# ethernet-connector.net
KiCad netlist of a schematic drawn in Altium Designer
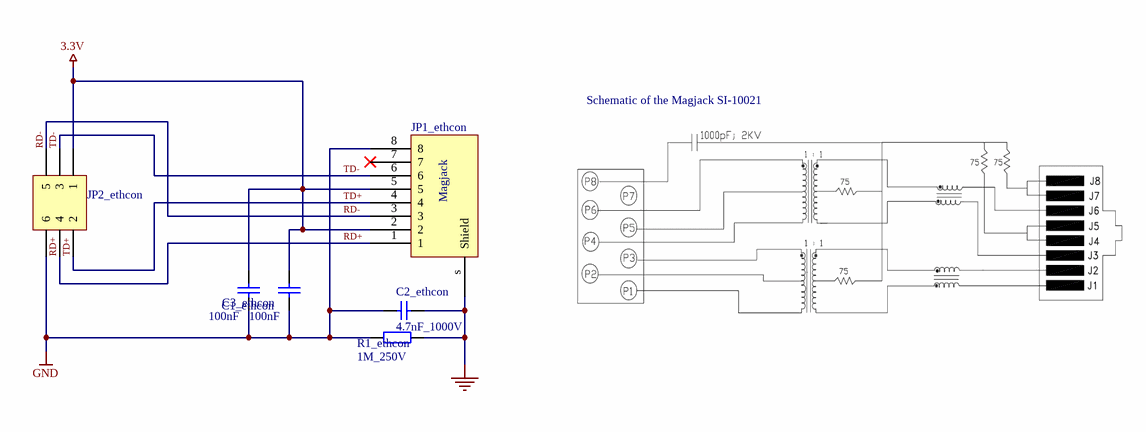
[diagram p0: ethernet-connector.SchDoc]

(export (version "E")
  (design (tool "Eeschema 10.0.6"))
  (components
    (comp (ref "1_ethcon")
      (value "CC License")
      (footprint "CC-License")
      (libsource (lib "gecko3-user") (part "CC License"))
    )
    (comp (ref "C1_ethcon")
      (value "100nF")
      (footprint "0402")
      (description "Capacitor")
      (fields
        (field (name "MANUFACTURER") "Murata")
        (field (name "PART NUMBER") "GRM155R71C104KA88D")
        (field (name "PUBLISHER") "Altium Limited")
      )
      (libsource (lib "Miscellaneous Devices") (part "Cap"))
    )
    (comp (ref "C2_ethcon")
      (value "4.7nF_1000V")
      (footprint "c-r5")
      (fields
        (field (name "MANUFACTURER") "Murata")
        (field (name "PART NUMBER") "DEBF33A472ZC1B")
        (field (name "Comment") "C")
      )
      (libsource (lib "gecko3-user") (part "C"))
    )
    (comp (ref "C3_ethcon")
      (value "100nF")
      (footprint "0402")
      (description "Capacitor")
      (fields
        (field (name "MANUFACTURER") "Murata")
        (field (name "PART NUMBER") "GRM155R71C104KA88D")
        (field (name "PUBLISHER") "Altium Limited")
      )
      (libsource (lib "Miscellaneous Devices") (part "Cap"))
    )
    (comp (ref "JP1_ethcon")
      (value "SI-10021")
      (footprint "SI-10021")
      (description "MagJack from Bel Stewart, single port RJ45 with magnetics, without LED's")
      (fields (field (name "MANUFACTURER") "Stewart"))
      (libsource (lib "gecko3-user") (part "SI-10021"))
    )
    (comp (ref "JP2_ethcon")
      (value "M22-2540305")
      (footprint "M22-2540305")
      (fields (field (name "MANUFACTURER") "HARWIN") (field (name "PART NUMBER") "M22F2040305"))
      (libsource (lib "gecko3-user") (part "M22-2540305"))
    )
    (comp (ref "R1_ethcon")
      (value "1M_250V")
      (footprint "CC3216-1206")
      (description "Resistor")
      (fields
        (field (name "MANUFACTURER") "Multicomp")
        (field (name "PART NUMBER") "MC 0.125W 1206 1% 1M")
        (field (name "PUBLISHER") "Altium Limited")
      )
      (libsource (lib "Miscellaneous Devices") (part "Res2"))
    )
  )
  (nets
    (net (code "1") (name "/RD+") (class "Default")
      (node (ref "JP1_ethcon") (pin "1") (pinfunction "1_1") (pintype "passive"))
      (node (ref "JP2_ethcon") (pin "4") (pinfunction "4_4") (pintype "passive"))
    )
    (net (code "2") (name "/RD-") (class "Default")
      (node (ref "JP1_ethcon") (pin "3") (pinfunction "3_3") (pintype "passive"))
      (node (ref "JP2_ethcon") (pin "5") (pinfunction "5_5") (pintype "passive"))
    )
    (net (code "3") (name "/TD+") (class "Default")
      (node (ref "JP1_ethcon") (pin "4") (pinfunction "4_4") (pintype "passive"))
      (node (ref "JP2_ethcon") (pin "2") (pinfunction "2_2") (pintype "passive"))
    )
    (net (code "4") (name "/TD-") (class "Default")
      (node (ref "JP1_ethcon") (pin "6") (pinfunction "6_6") (pintype "passive"))
      (node (ref "JP2_ethcon") (pin "3") (pinfunction "3_3") (pintype "passive"))
    )
    (net (code "5") (name "3.3V") (class "Default")
      (node (ref "C1_ethcon") (pin "2") (pinfunction "2_2") (pintype "passive"))
      (node (ref "C3_ethcon") (pin "2") (pinfunction "2_2") (pintype "passive"))
      (node (ref "JP1_ethcon") (pin "2") (pinfunction "2_2") (pintype "passive"))
      (node (ref "JP1_ethcon") (pin "5") (pinfunction "5_5") (pintype "passive"))
      (node (ref "JP2_ethcon") (pin "1") (pinfunction "1_1") (pintype "passive"))
    )
    (net (code "6") (name "Earth") (class "Default")
      (node (ref "C2_ethcon") (pin "1") (pinfunction "1_1") (pintype "passive"))
      (node (ref "JP1_ethcon") (pin "s") (pinfunction "Shield_s") (pintype "passive"))
      (node (ref "R1_ethcon") (pin "1") (pinfunction "1_1") (pintype "passive"))
    )
    (net (code "7") (name "GND") (class "Default")
      (node (ref "C1_ethcon") (pin "1") (pinfunction "1_1") (pintype "passive"))
      (node (ref "C2_ethcon") (pin "2") (pinfunction "2_2") (pintype "passive"))
      (node (ref "C3_ethcon") (pin "1") (pinfunction "1_1") (pintype "passive"))
      (node (ref "JP1_ethcon") (pin "8") (pinfunction "8_8") (pintype "passive"))
      (node (ref "JP2_ethcon") (pin "6") (pinfunction "6_6") (pintype "passive"))
      (node (ref "R1_ethcon") (pin "2") (pinfunction "2_2") (pintype "passive"))
    )
    (net (code "8") (name "unconnected-(JP1_ethcon-Pad7)") (class "Default")
      (node (ref "JP1_ethcon") (pin "7") (pinfunction "7_7") (pintype "passive+no_connect"))
    )
  )
)
